# Backplane_Breakout_Adapter_Connectors.net
KiCad netlist of a schematic drawn in Altium Designer
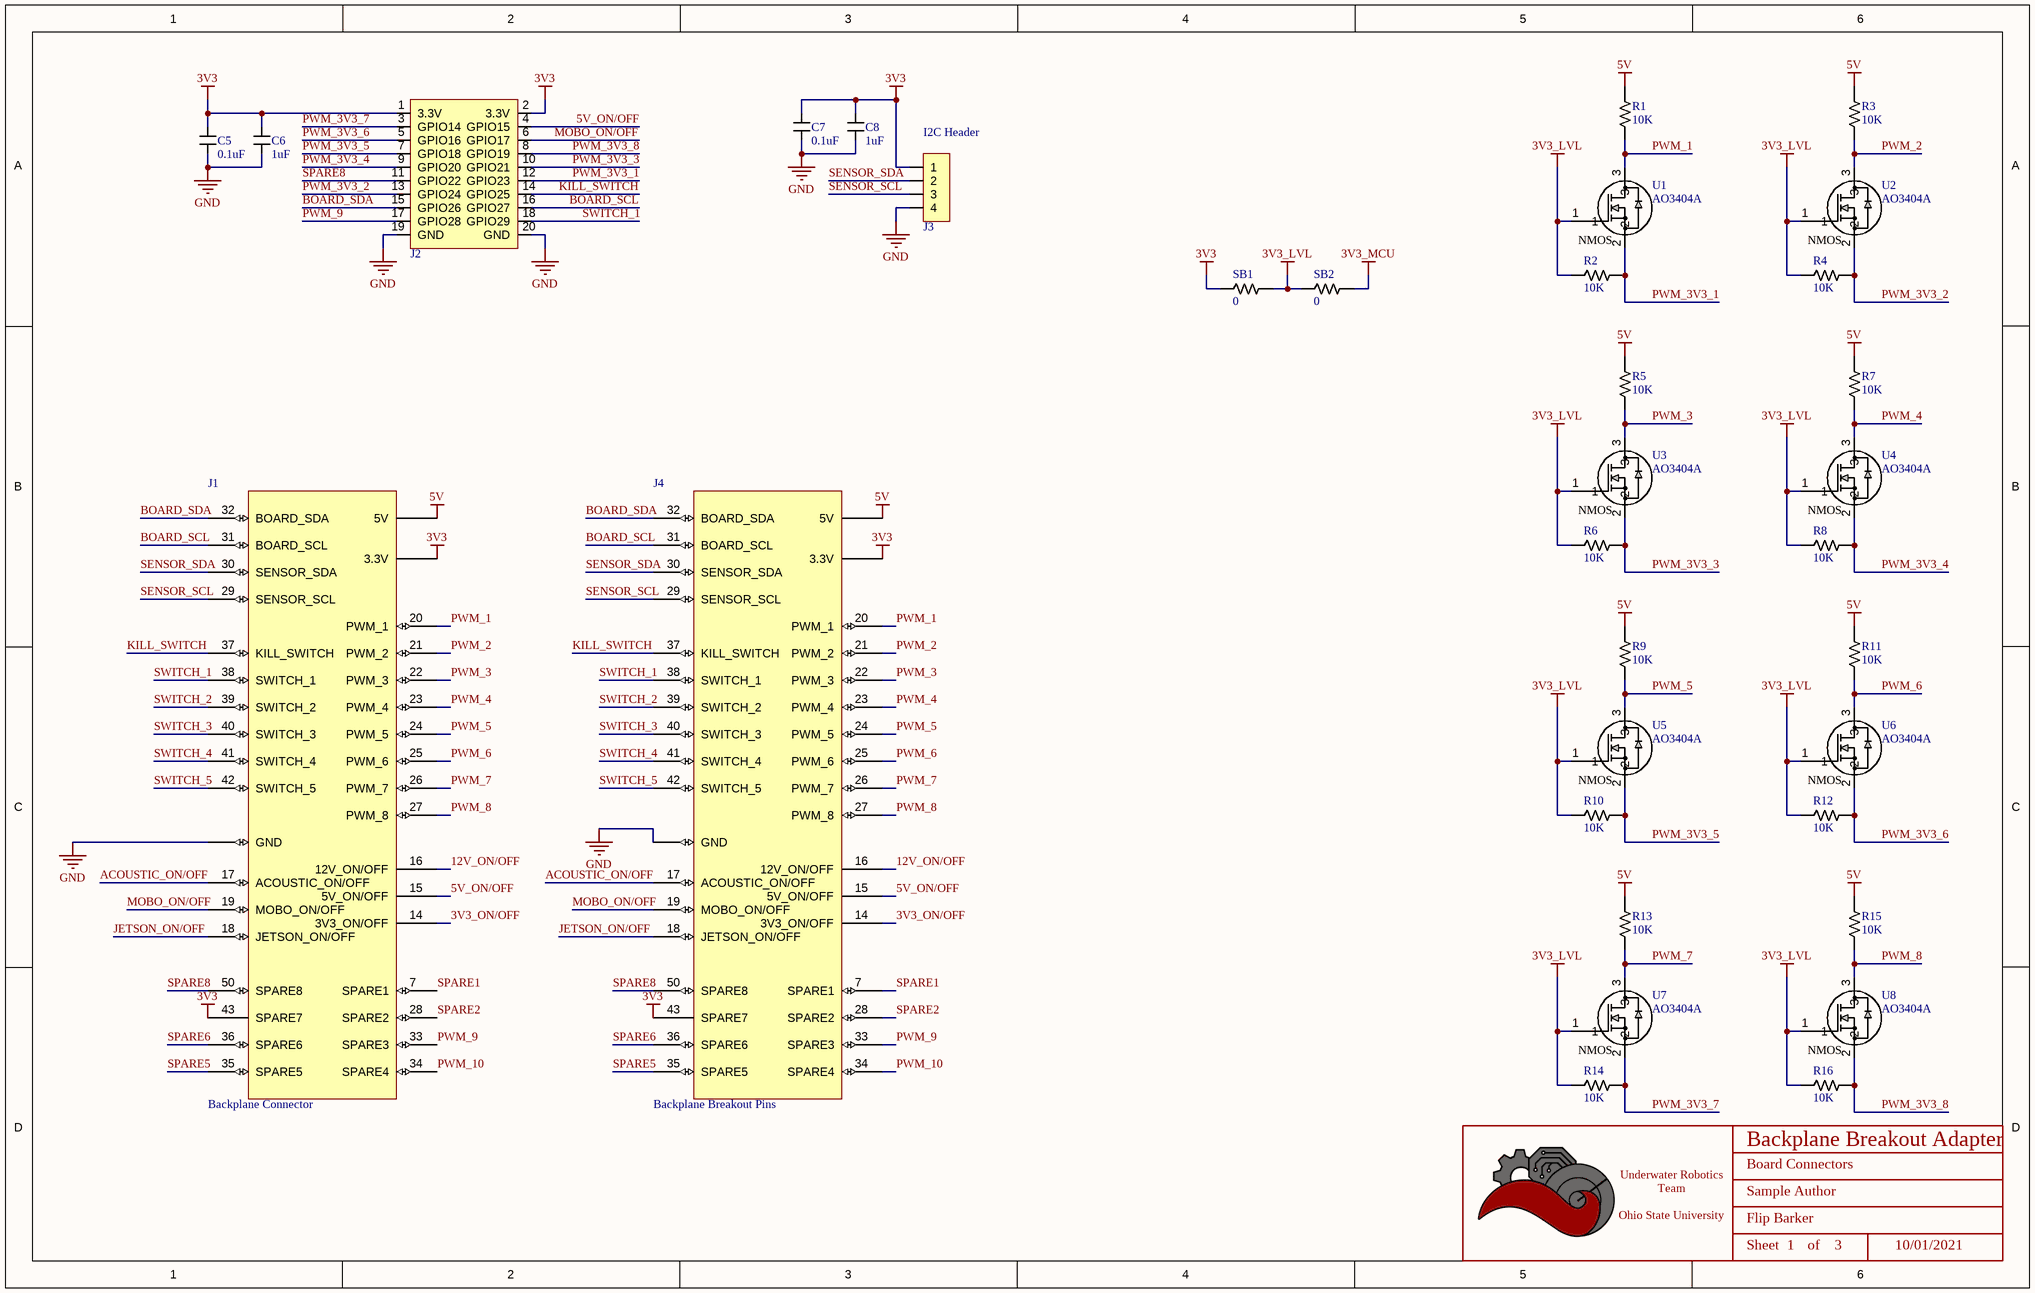
[diagram p0: Backplane_Breakout_Adapter_Connectors.SchDoc]

(export (version "E")
  (design (tool "Eeschema 10.0.6"))
  (components
    (comp (ref "*")
      (value "Title_Block")
      (footprint "LOGO")
      (description "UWRT Schematic Title Block Template\r\n\r\nCreated June 2021, Dylan Trainor")
      (libsource (lib "UWRT") (part "Title_Block"))
    )
    (comp (ref "C5")
      (value "0.1uF")
      (footprint "CAPACITOR_0603")
      (description "Cap 100nF 6.3V +/-10%\r\nCeramic 0603")
      (fields
        (field (name "TOLERANCE") "+/- 10%")
        (field (name "VOLTAGE") "6.3V")
        (field (name "MADE BY") "Flip B")
      )
      (libsource (lib "Capacitors") (part "CAPACITOR_0.1uF_0603"))
    )
    (comp (ref "C6")
      (value "1uF")
      (footprint "CAPACITOR_0603")
      (description "Cap 1uF 16V +/-10%\r\nCeramic 0603")
      (fields
        (field (name "TOLERANCE") "+/- 10%")
        (field (name "VOLTAGE") "16V")
        (field (name "MADE BY") "Flip B")
      )
      (libsource (lib "Capacitors") (part "CAPACITOR_1uF_0603"))
    )
    (comp (ref "C7")
      (value "0.1uF")
      (footprint "CAPACITOR_0603")
      (description "Cap 100nF 6.3V +/-10%\r\nCeramic 0603")
      (fields
        (field (name "TOLERANCE") "+/- 10%")
        (field (name "VOLTAGE") "6.3V")
        (field (name "MADE BY") "Flip B")
      )
      (libsource (lib "Capacitors") (part "CAPACITOR_0.1uF_0603"))
    )
    (comp (ref "C8")
      (value "1uF")
      (footprint "CAPACITOR_0603")
      (description "Cap 1uF 16V +/-10%\r\nCeramic 0603")
      (fields
        (field (name "TOLERANCE") "+/- 10%")
        (field (name "VOLTAGE") "16V")
        (field (name "MADE BY") "Flip B")
      )
      (libsource (lib "Capacitors") (part "CAPACITOR_1uF_0603"))
    )
    (comp (ref "J1")
      (value "Backplane Connector")
      (footprint "BACKPLANE_EDGE_CONN")
      (description "Titan Backplane Edge Connector")
      (libsource (lib "Connectors") (part "BACKBOARD_EDGE_CONN"))
    )
    (comp (ref "J2")
      (value "RP2040 GPIO Header")
      (footprint "HEADER_MIRRORED_2x10PIN_2.54MM")
      (description "CONN HEADER VERT 20POS 2.54MM")
      (fields (field (name "MADE BY") "Robert Pafford"))
      (libsource (lib "Connectors") (part "HEADER_2x10PIN_2.54MM_RP2040_GPIO"))
    )
    (comp (ref "J3")
      (value "CONN HEADER VERT 4POS 2.54MM")
      (footprint "HEADER_MIRRORED_4PIN_2.54MM")
      (fields (field (name "MADE BY") "Robert Pafford"))
      (libsource (lib "Connectors") (part "HEADER_4PIN_2.54MM"))
    )
    (comp (ref "J4")
      (value "Backplane Breakout Pins")
      (footprint "HEADER_2X28PIN_2.54MM")
      (description "Titan Backplane Edge Connector")
      (libsource (lib "Connectors") (part "BACKBOARD_EDGE_CONN"))
    )
    (comp (ref "R1")
      (value "10k Ohm 5% 1/10W")
      (footprint "RESISTOR_0603")
      (description "RES 10k OHM 5% 1/10W 0603")
      (fields
        (field (name "TOLERANCE") "+/- 5%")
        (field (name "VALUE  (OHMS)") "10K")
        (field (name "MADE BY") "Robert Pafford")
      )
      (libsource (lib "Resistors") (part "RESISTOR_10K_0603"))
    )
    (comp (ref "R2")
      (value "10k Ohm 5% 1/10W")
      (footprint "RESISTOR_0603")
      (description "RES 10k OHM 5% 1/10W 0603")
      (fields
        (field (name "TOLERANCE") "+/- 5%")
        (field (name "VALUE  (OHMS)") "10K")
        (field (name "MADE BY") "Robert Pafford")
      )
      (libsource (lib "Resistors") (part "RESISTOR_10K_0603"))
    )
    (comp (ref "R3")
      (value "10k Ohm 5% 1/10W")
      (footprint "RESISTOR_0603")
      (description "RES 10k OHM 5% 1/10W 0603")
      (fields
        (field (name "TOLERANCE") "+/- 5%")
        (field (name "VALUE  (OHMS)") "10K")
        (field (name "MADE BY") "Robert Pafford")
      )
      (libsource (lib "Resistors") (part "RESISTOR_10K_0603"))
    )
    (comp (ref "R4")
      (value "10k Ohm 5% 1/10W")
      (footprint "RESISTOR_0603")
      (description "RES 10k OHM 5% 1/10W 0603")
      (fields
        (field (name "TOLERANCE") "+/- 5%")
        (field (name "VALUE  (OHMS)") "10K")
        (field (name "MADE BY") "Robert Pafford")
      )
      (libsource (lib "Resistors") (part "RESISTOR_10K_0603"))
    )
    (comp (ref "R5")
      (value "10k Ohm 5% 1/10W")
      (footprint "RESISTOR_0603")
      (description "RES 10k OHM 5% 1/10W 0603")
      (fields
        (field (name "TOLERANCE") "+/- 5%")
        (field (name "VALUE  (OHMS)") "10K")
        (field (name "MADE BY") "Robert Pafford")
      )
      (libsource (lib "Resistors") (part "RESISTOR_10K_0603"))
    )
    (comp (ref "R6")
      (value "10k Ohm 5% 1/10W")
      (footprint "RESISTOR_0603")
      (description "RES 10k OHM 5% 1/10W 0603")
      (fields
        (field (name "TOLERANCE") "+/- 5%")
        (field (name "VALUE  (OHMS)") "10K")
        (field (name "MADE BY") "Robert Pafford")
      )
      (libsource (lib "Resistors") (part "RESISTOR_10K_0603"))
    )
    (comp (ref "R7")
      (value "10k Ohm 5% 1/10W")
      (footprint "RESISTOR_0603")
      (description "RES 10k OHM 5% 1/10W 0603")
      (fields
        (field (name "TOLERANCE") "+/- 5%")
        (field (name "VALUE  (OHMS)") "10K")
        (field (name "MADE BY") "Robert Pafford")
      )
      (libsource (lib "Resistors") (part "RESISTOR_10K_0603"))
    )
    (comp (ref "R8")
      (value "10k Ohm 5% 1/10W")
      (footprint "RESISTOR_0603")
      (description "RES 10k OHM 5% 1/10W 0603")
      (fields
        (field (name "TOLERANCE") "+/- 5%")
        (field (name "VALUE  (OHMS)") "10K")
        (field (name "MADE BY") "Robert Pafford")
      )
      (libsource (lib "Resistors") (part "RESISTOR_10K_0603"))
    )
    (comp (ref "R9")
      (value "10k Ohm 5% 1/10W")
      (footprint "RESISTOR_0603")
      (description "RES 10k OHM 5% 1/10W 0603")
      (fields
        (field (name "TOLERANCE") "+/- 5%")
        (field (name "VALUE  (OHMS)") "10K")
        (field (name "MADE BY") "Robert Pafford")
      )
      (libsource (lib "Resistors") (part "RESISTOR_10K_0603"))
    )
    (comp (ref "R10")
      (value "10k Ohm 5% 1/10W")
      (footprint "RESISTOR_0603")
      (description "RES 10k OHM 5% 1/10W 0603")
      (fields
        (field (name "TOLERANCE") "+/- 5%")
        (field (name "VALUE  (OHMS)") "10K")
        (field (name "MADE BY") "Robert Pafford")
      )
      (libsource (lib "Resistors") (part "RESISTOR_10K_0603"))
    )
    (comp (ref "R11")
      (value "10k Ohm 5% 1/10W")
      (footprint "RESISTOR_0603")
      (description "RES 10k OHM 5% 1/10W 0603")
      (fields
        (field (name "TOLERANCE") "+/- 5%")
        (field (name "VALUE  (OHMS)") "10K")
        (field (name "MADE BY") "Robert Pafford")
      )
      (libsource (lib "Resistors") (part "RESISTOR_10K_0603"))
    )
    (comp (ref "R12")
      (value "10k Ohm 5% 1/10W")
      (footprint "RESISTOR_0603")
      (description "RES 10k OHM 5% 1/10W 0603")
      (fields
        (field (name "TOLERANCE") "+/- 5%")
        (field (name "VALUE  (OHMS)") "10K")
        (field (name "MADE BY") "Robert Pafford")
      )
      (libsource (lib "Resistors") (part "RESISTOR_10K_0603"))
    )
    (comp (ref "R13")
      (value "10k Ohm 5% 1/10W")
      (footprint "RESISTOR_0603")
      (description "RES 10k OHM 5% 1/10W 0603")
      (fields
        (field (name "TOLERANCE") "+/- 5%")
        (field (name "VALUE  (OHMS)") "10K")
        (field (name "MADE BY") "Robert Pafford")
      )
      (libsource (lib "Resistors") (part "RESISTOR_10K_0603"))
    )
    (comp (ref "R14")
      (value "10k Ohm 5% 1/10W")
      (footprint "RESISTOR_0603")
      (description "RES 10k OHM 5% 1/10W 0603")
      (fields
        (field (name "TOLERANCE") "+/- 5%")
        (field (name "VALUE  (OHMS)") "10K")
        (field (name "MADE BY") "Robert Pafford")
      )
      (libsource (lib "Resistors") (part "RESISTOR_10K_0603"))
    )
    (comp (ref "R15")
      (value "10k Ohm 5% 1/10W")
      (footprint "RESISTOR_0603")
      (description "RES 10k OHM 5% 1/10W 0603")
      (fields
        (field (name "TOLERANCE") "+/- 5%")
        (field (name "VALUE  (OHMS)") "10K")
        (field (name "MADE BY") "Robert Pafford")
      )
      (libsource (lib "Resistors") (part "RESISTOR_10K_0603"))
    )
    (comp (ref "R16")
      (value "10k Ohm 5% 1/10W")
      (footprint "RESISTOR_0603")
      (description "RES 10k OHM 5% 1/10W 0603")
      (fields
        (field (name "TOLERANCE") "+/- 5%")
        (field (name "VALUE  (OHMS)") "10K")
        (field (name "MADE BY") "Robert Pafford")
      )
      (libsource (lib "Resistors") (part "RESISTOR_10K_0603"))
    )
    (comp (ref "SB1")
      (value "0 Ohm Jumper No Fit")
      (footprint "RESISTOR_0603")
      (description "0 Ohm Jumper No Fit for Solder Bridge")
      (fields (field (name "VALUE  (OHMS)") "0") (field (name "MADE BY") "Robert Pafford"))
      (libsource (lib "Resistors") (part "JUMPER_0_0603"))
    )
    (comp (ref "SB2")
      (value "0 Ohm Jumper No Fit")
      (footprint "RESISTOR_0603")
      (description "0 Ohm Jumper No Fit for Solder Bridge")
      (fields (field (name "VALUE  (OHMS)") "0") (field (name "MADE BY") "Robert Pafford"))
      (libsource (lib "Resistors") (part "JUMPER_0_0603"))
    )
    (comp (ref "U1")
      (value "AO3404A")
      (footprint "SOT-23-3")
      (description "N-Channel 30 V 5.8A (Ta) 1.4W (Ta) Surface Mount SOT-23-3")
      (fields (field (name "CREATED BY") "Dylan T"))
      (libsource (lib "Transistors") (part "AO3404A"))
    )
    (comp (ref "U2")
      (value "AO3404A")
      (footprint "SOT-23-3")
      (description "N-Channel 30 V 5.8A (Ta) 1.4W (Ta) Surface Mount SOT-23-3")
      (fields (field (name "CREATED BY") "Dylan T"))
      (libsource (lib "Transistors") (part "AO3404A"))
    )
    (comp (ref "U3")
      (value "AO3404A")
      (footprint "SOT-23-3")
      (description "N-Channel 30 V 5.8A (Ta) 1.4W (Ta) Surface Mount SOT-23-3")
      (fields (field (name "CREATED BY") "Dylan T"))
      (libsource (lib "Transistors") (part "AO3404A"))
    )
    (comp (ref "U4")
      (value "AO3404A")
      (footprint "SOT-23-3")
      (description "N-Channel 30 V 5.8A (Ta) 1.4W (Ta) Surface Mount SOT-23-3")
      (fields (field (name "CREATED BY") "Dylan T"))
      (libsource (lib "Transistors") (part "AO3404A"))
    )
    (comp (ref "U5")
      (value "AO3404A")
      (footprint "SOT-23-3")
      (description "N-Channel 30 V 5.8A (Ta) 1.4W (Ta) Surface Mount SOT-23-3")
      (fields (field (name "CREATED BY") "Dylan T"))
      (libsource (lib "Transistors") (part "AO3404A"))
    )
    (comp (ref "U6")
      (value "AO3404A")
      (footprint "SOT-23-3")
      (description "N-Channel 30 V 5.8A (Ta) 1.4W (Ta) Surface Mount SOT-23-3")
      (fields (field (name "CREATED BY") "Dylan T"))
      (libsource (lib "Transistors") (part "AO3404A"))
    )
    (comp (ref "U7")
      (value "AO3404A")
      (footprint "SOT-23-3")
      (description "N-Channel 30 V 5.8A (Ta) 1.4W (Ta) Surface Mount SOT-23-3")
      (fields (field (name "CREATED BY") "Dylan T"))
      (libsource (lib "Transistors") (part "AO3404A"))
    )
    (comp (ref "U8")
      (value "AO3404A")
      (footprint "SOT-23-3")
      (description "N-Channel 30 V 5.8A (Ta) 1.4W (Ta) Surface Mount SOT-23-3")
      (fields (field (name "CREATED BY") "Dylan T"))
      (libsource (lib "Transistors") (part "AO3404A"))
    )
  )
  (nets
    (net (code "1") (name "/3V3_ON{slash}OFF") (class "Default")
      (node (ref "J1") (pin "14") (pinfunction "3V3_ON/OFF_14") (pintype "power_in"))
      (node (ref "J4") (pin "14") (pinfunction "3V3_ON/OFF_14") (pintype "power_in"))
    )
    (net (code "2") (name "/5V_ON{slash}OFF") (class "Default")
      (node (ref "J1") (pin "15") (pinfunction "5V_ON/OFF_15") (pintype "power_in"))
      (node (ref "J2") (pin "4") (pinfunction "GPIO15_4") (pintype "bidirectional"))
      (node (ref "J4") (pin "15") (pinfunction "5V_ON/OFF_15") (pintype "power_in"))
    )
    (net (code "3") (name "/12V_ON{slash}OFF") (class "Default")
      (node (ref "J1") (pin "16") (pinfunction "12V_ON/OFF_16") (pintype "power_in"))
      (node (ref "J4") (pin "16") (pinfunction "12V_ON/OFF_16") (pintype "power_in"))
    )
    (net (code "4") (name "/ACOUSTIC_ON{slash}OFF") (class "Default")
      (node (ref "J1") (pin "17") (pinfunction "ACOUSTIC_ON/OFF_17") (pintype "bidirectional"))
      (node (ref "J4") (pin "17") (pinfunction "ACOUSTIC_ON/OFF_17") (pintype "bidirectional"))
    )
    (net (code "5") (name "/BOARD_SCL") (class "Default")
      (node (ref "J1") (pin "31") (pinfunction "BOARD_SCL_31") (pintype "bidirectional"))
      (node (ref "J2") (pin "16") (pinfunction "GPIO27_16") (pintype "bidirectional"))
      (node (ref "J4") (pin "31") (pinfunction "BOARD_SCL_31") (pintype "bidirectional"))
    )
    (net (code "6") (name "/BOARD_SDA") (class "Default")
      (node (ref "J1") (pin "32") (pinfunction "BOARD_SDA_32") (pintype "bidirectional"))
      (node (ref "J2") (pin "15") (pinfunction "GPIO26_15") (pintype "bidirectional"))
      (node (ref "J4") (pin "32") (pinfunction "BOARD_SDA_32") (pintype "bidirectional"))
    )
    (net (code "7") (name "/JETSON_ON{slash}OFF") (class "Default")
      (node (ref "J1") (pin "18") (pinfunction "JETSON_ON/OFF_18") (pintype "bidirectional"))
      (node (ref "J4") (pin "18") (pinfunction "JETSON_ON/OFF_18") (pintype "bidirectional"))
    )
    (net (code "8") (name "/KILL_SWITCH") (class "Default")
      (node (ref "J1") (pin "37") (pinfunction "KILL_SWITCH_37") (pintype "bidirectional"))
      (node (ref "J2") (pin "14") (pinfunction "GPIO25_14") (pintype "bidirectional"))
      (node (ref "J4") (pin "37") (pinfunction "KILL_SWITCH_37") (pintype "bidirectional"))
    )
    (net (code "9") (name "/MOBO_ON{slash}OFF") (class "Default")
      (node (ref "J1") (pin "19") (pinfunction "MOBO_ON/OFF_19") (pintype "bidirectional"))
      (node (ref "J2") (pin "6") (pinfunction "GPIO17_6") (pintype "bidirectional"))
      (node (ref "J4") (pin "19") (pinfunction "MOBO_ON/OFF_19") (pintype "bidirectional"))
    )
    (net (code "10") (name "/PWM_1") (class "Default")
      (node (ref "J1") (pin "20") (pinfunction "PWM_1_20") (pintype "bidirectional"))
      (node (ref "J4") (pin "20") (pinfunction "PWM_1_20") (pintype "bidirectional"))
      (node (ref "R1") (pin "2") (pinfunction "2_2") (pintype "passive"))
      (node (ref "U1") (pin "3") (pinfunction "3_3") (pintype "passive"))
    )
    (net (code "11") (name "/PWM_2") (class "Default")
      (node (ref "J1") (pin "21") (pinfunction "PWM_2_21") (pintype "bidirectional"))
      (node (ref "J4") (pin "21") (pinfunction "PWM_2_21") (pintype "bidirectional"))
      (node (ref "R3") (pin "2") (pinfunction "2_2") (pintype "passive"))
      (node (ref "U2") (pin "3") (pinfunction "3_3") (pintype "passive"))
    )
    (net (code "12") (name "/PWM_3") (class "Default")
      (node (ref "J1") (pin "22") (pinfunction "PWM_3_22") (pintype "bidirectional"))
      (node (ref "J4") (pin "22") (pinfunction "PWM_3_22") (pintype "bidirectional"))
      (node (ref "R5") (pin "2") (pinfunction "2_2") (pintype "passive"))
      (node (ref "U3") (pin "3") (pinfunction "3_3") (pintype "passive"))
    )
    (net (code "13") (name "/PWM_3V3_1") (class "Default")
      (node (ref "J2") (pin "12") (pinfunction "GPIO23_12") (pintype "bidirectional"))
      (node (ref "R2") (pin "1") (pinfunction "1_1") (pintype "passive"))
      (node (ref "U1") (pin "2") (pinfunction "2_2") (pintype "passive"))
    )
    (net (code "14") (name "/PWM_3V3_2") (class "Default")
      (node (ref "J2") (pin "13") (pinfunction "GPIO24_13") (pintype "bidirectional"))
      (node (ref "R4") (pin "1") (pinfunction "1_1") (pintype "passive"))
      (node (ref "U2") (pin "2") (pinfunction "2_2") (pintype "passive"))
    )
    (net (code "15") (name "/PWM_3V3_3") (class "Default")
      (node (ref "J2") (pin "10") (pinfunction "GPIO21_10") (pintype "bidirectional"))
      (node (ref "R6") (pin "1") (pinfunction "1_1") (pintype "passive"))
      (node (ref "U3") (pin "2") (pinfunction "2_2") (pintype "passive"))
    )
    (net (code "16") (name "/PWM_3V3_4") (class "Default")
      (node (ref "J2") (pin "9") (pinfunction "GPIO20_9") (pintype "bidirectional"))
      (node (ref "R8") (pin "1") (pinfunction "1_1") (pintype "passive"))
      (node (ref "U4") (pin "2") (pinfunction "2_2") (pintype "passive"))
    )
    (net (code "17") (name "/PWM_3V3_5") (class "Default")
      (node (ref "J2") (pin "7") (pinfunction "GPIO18_7") (pintype "bidirectional"))
      (node (ref "R10") (pin "1") (pinfunction "1_1") (pintype "passive"))
      (node (ref "U5") (pin "2") (pinfunction "2_2") (pintype "passive"))
    )
    (net (code "18") (name "/PWM_3V3_6") (class "Default")
      (node (ref "J2") (pin "5") (pinfunction "GPIO16_5") (pintype "bidirectional"))
      (node (ref "R12") (pin "1") (pinfunction "1_1") (pintype "passive"))
      (node (ref "U6") (pin "2") (pinfunction "2_2") (pintype "passive"))
    )
    (net (code "19") (name "/PWM_3V3_7") (class "Default")
      (node (ref "J2") (pin "3") (pinfunction "GPIO14_3") (pintype "bidirectional"))
      (node (ref "R14") (pin "1") (pinfunction "1_1") (pintype "passive"))
      (node (ref "U7") (pin "2") (pinfunction "2_2") (pintype "passive"))
    )
    (net (code "20") (name "/PWM_3V3_8") (class "Default")
      (node (ref "J2") (pin "8") (pinfunction "GPIO19_8") (pintype "bidirectional"))
      (node (ref "R16") (pin "1") (pinfunction "1_1") (pintype "passive"))
      (node (ref "U8") (pin "2") (pinfunction "2_2") (pintype "passive"))
    )
    (net (code "21") (name "/PWM_4") (class "Default")
      (node (ref "J1") (pin "23") (pinfunction "PWM_4_23") (pintype "bidirectional"))
      (node (ref "J4") (pin "23") (pinfunction "PWM_4_23") (pintype "bidirectional"))
      (node (ref "R7") (pin "2") (pinfunction "2_2") (pintype "passive"))
      (node (ref "U4") (pin "3") (pinfunction "3_3") (pintype "passive"))
    )
    (net (code "22") (name "/PWM_5") (class "Default")
      (node (ref "J1") (pin "24") (pinfunction "PWM_5_24") (pintype "bidirectional"))
      (node (ref "J4") (pin "24") (pinfunction "PWM_5_24") (pintype "bidirectional"))
      (node (ref "R9") (pin "2") (pinfunction "2_2") (pintype "passive"))
      (node (ref "U5") (pin "3") (pinfunction "3_3") (pintype "passive"))
    )
    (net (code "23") (name "/PWM_6") (class "Default")
      (node (ref "J1") (pin "25") (pinfunction "PWM_6_25") (pintype "bidirectional"))
      (node (ref "J4") (pin "25") (pinfunction "PWM_6_25") (pintype "bidirectional"))
      (node (ref "R11") (pin "2") (pinfunction "2_2") (pintype "passive"))
      (node (ref "U6") (pin "3") (pinfunction "3_3") (pintype "passive"))
    )
    (net (code "24") (name "/PWM_7") (class "Default")
      (node (ref "J1") (pin "26") (pinfunction "PWM_7_26") (pintype "bidirectional"))
      (node (ref "J4") (pin "26") (pinfunction "PWM_7_26") (pintype "bidirectional"))
      (node (ref "R13") (pin "2") (pinfunction "2_2") (pintype "passive"))
      (node (ref "U7") (pin "3") (pinfunction "3_3") (pintype "passive"))
    )
    (net (code "25") (name "/PWM_8") (class "Default")
      (node (ref "J1") (pin "27") (pinfunction "PWM_8_27") (pintype "bidirectional"))
      (node (ref "J4") (pin "27") (pinfunction "PWM_8_27") (pintype "bidirectional"))
      (node (ref "R15") (pin "2") (pinfunction "2_2") (pintype "passive"))
      (node (ref "U8") (pin "3") (pinfunction "3_3") (pintype "passive"))
    )
    (net (code "26") (name "/PWM_9") (class "Default")
      (node (ref "J1") (pin "33") (pinfunction "SPARE3_33") (pintype "bidirectional"))
      (node (ref "J2") (pin "17") (pinfunction "GPIO28_17") (pintype "bidirectional"))
      (node (ref "J4") (pin "33") (pinfunction "SPARE3_33") (pintype "bidirectional"))
    )
    (net (code "27") (name "/PWM_10") (class "Default")
      (node (ref "J1") (pin "34") (pinfunction "SPARE4_34") (pintype "bidirectional"))
      (node (ref "J4") (pin "34") (pinfunction "SPARE4_34") (pintype "bidirectional"))
    )
    (net (code "28") (name "/SENSOR_SCL") (class "Default")
      (node (ref "J1") (pin "29") (pinfunction "SENSOR_SCL_29") (pintype "bidirectional"))
      (node (ref "J3") (pin "3") (pinfunction "3_3") (pintype "passive"))
      (node (ref "J4") (pin "29") (pinfunction "SENSOR_SCL_29") (pintype "bidirectional"))
    )
    (net (code "29") (name "/SENSOR_SDA") (class "Default")
      (node (ref "J1") (pin "30") (pinfunction "SENSOR_SDA_30") (pintype "bidirectional"))
      (node (ref "J3") (pin "2") (pinfunction "2_2") (pintype "passive"))
      (node (ref "J4") (pin "30") (pinfunction "SENSOR_SDA_30") (pintype "bidirectional"))
    )
    (net (code "30") (name "/SPARE1") (class "Default")
      (node (ref "J1") (pin "7") (pinfunction "SPARE1_7") (pintype "bidirectional"))
      (node (ref "J4") (pin "7") (pinfunction "SPARE1_7") (pintype "bidirectional"))
    )
    (net (code "31") (name "/SPARE2") (class "Default")
      (node (ref "J1") (pin "28") (pinfunction "SPARE2_28") (pintype "bidirectional"))
      (node (ref "J4") (pin "28") (pinfunction "SPARE2_28") (pintype "bidirectional"))
    )
    (net (code "32") (name "/SPARE5") (class "Default")
      (node (ref "J1") (pin "35") (pinfunction "SPARE5_35") (pintype "bidirectional"))
      (node (ref "J4") (pin "35") (pinfunction "SPARE5_35") (pintype "bidirectional"))
    )
    (net (code "33") (name "/SPARE6") (class "Default")
      (node (ref "J1") (pin "36") (pinfunction "SPARE6_36") (pintype "bidirectional"))
      (node (ref "J4") (pin "36") (pinfunction "SPARE6_36") (pintype "bidirectional"))
    )
    (net (code "34") (name "/SPARE8") (class "Default")
      (node (ref "J1") (pin "50") (pinfunction "SPARE8_50") (pintype "bidirectional"))
      (node (ref "J2") (pin "11") (pinfunction "GPIO22_11") (pintype "bidirectional"))
      (node (ref "J4") (pin "50") (pinfunction "SPARE8_50") (pintype "bidirectional"))
    )
    (net (code "35") (name "/SWITCH_1") (class "Default")
      (node (ref "J1") (pin "38") (pinfunction "SWITCH_1_38") (pintype "bidirectional"))
      (node (ref "J2") (pin "18") (pinfunction "GPIO29_18") (pintype "bidirectional"))
      (node (ref "J4") (pin "38") (pinfunction "SWITCH_1_38") (pintype "bidirectional"))
    )
    (net (code "36") (name "/SWITCH_2") (class "Default")
      (node (ref "J1") (pin "39") (pinfunction "SWITCH_2_39") (pintype "bidirectional"))
      (node (ref "J4") (pin "39") (pinfunction "SWITCH_2_39") (pintype "bidirectional"))
    )
    (net (code "37") (name "/SWITCH_3") (class "Default")
      (node (ref "J1") (pin "40") (pinfunction "SWITCH_3_40") (pintype "bidirectional"))
      (node (ref "J4") (pin "40") (pinfunction "SWITCH_3_40") (pintype "bidirectional"))
    )
    (net (code "38") (name "/SWITCH_4") (class "Default")
      (node (ref "J1") (pin "41") (pinfunction "SWITCH_4_41") (pintype "bidirectional"))
      (node (ref "J4") (pin "41") (pinfunction "SWITCH_4_41") (pintype "bidirectional"))
    )
    (net (code "39") (name "/SWITCH_5") (class "Default")
      (node (ref "J1") (pin "42") (pinfunction "SWITCH_5_42") (pintype "bidirectional"))
      (node (ref "J4") (pin "42") (pinfunction "SWITCH_5_42") (pintype "bidirectional"))
    )
    (net (code "40") (name "3V3") (class "Default")
      (node (ref "C5") (pin "1") (pinfunction "1_1") (pintype "passive"))
      (node (ref "C6") (pin "1") (pinfunction "1_1") (pintype "passive"))
      (node (ref "C7") (pin "1") (pinfunction "1_1") (pintype "passive"))
      (node (ref "C8") (pin "1") (pinfunction "1_1") (pintype "passive"))
      (node (ref "J1") (pin "1*6") (pinfunction "3.3V_1*6") (pintype "power_in"))
      (node (ref "J1") (pin "43") (pinfunction "SPARE7_43") (pintype "power_in"))
      (node (ref "J2") (pin "1") (pinfunction "3.3V_1") (pintype "power_in"))
      (node (ref "J2") (pin "2") (pinfunction "3.3V_2") (pintype "power_in"))
      (node (ref "J3") (pin "1") (pinfunction "1_1") (pintype "passive"))
      (node (ref "J4") (pin "1*6") (pinfunction "3.3V_1*6") (pintype "power_in"))
      (node (ref "J4") (pin "43") (pinfunction "SPARE7_43") (pintype "power_in"))
      (node (ref "SB1") (pin "2") (pinfunction "2_2") (pintype "passive"))
    )
    (net (code "41") (name "3V3_LVL") (class "Default")
      (node (ref "R10") (pin "2") (pinfunction "2_2") (pintype "passive"))
      (node (ref "R12") (pin "2") (pinfunction "2_2") (pintype "passive"))
      (node (ref "R14") (pin "2") (pinfunction "2_2") (pintype "passive"))
      (node (ref "R16") (pin "2") (pinfunction "2_2") (pintype "passive"))
      (node (ref "R2") (pin "2") (pinfunction "2_2") (pintype "passive"))
      (node (ref "R4") (pin "2") (pinfunction "2_2") (pintype "passive"))
      (node (ref "R6") (pin "2") (pinfunction "2_2") (pintype "passive"))
      (node (ref "R8") (pin "2") (pinfunction "2_2") (pintype "passive"))
      (node (ref "SB1") (pin "1") (pinfunction "1_1") (pintype "passive"))
      (node (ref "SB2") (pin "2") (pinfunction "2_2") (pintype "passive"))
      (node (ref "U1") (pin "1") (pinfunction "1_1") (pintype "passive"))
      (node (ref "U2") (pin "1") (pinfunction "1_1") (pintype "passive"))
      (node (ref "U3") (pin "1") (pinfunction "1_1") (pintype "passive"))
      (node (ref "U4") (pin "1") (pinfunction "1_1") (pintype "passive"))
      (node (ref "U5") (pin "1") (pinfunction "1_1") (pintype "passive"))
      (node (ref "U6") (pin "1") (pinfunction "1_1") (pintype "passive"))
      (node (ref "U7") (pin "1") (pinfunction "1_1") (pintype "passive"))
      (node (ref "U8") (pin "1") (pinfunction "1_1") (pintype "passive"))
    )
    (net (code "42") (name "3V3_MCU") (class "Default")
      (node (ref "SB2") (pin "1") (pinfunction "1_1") (pintype "passive"))
    )
    (net (code "43") (name "5V") (class "Default")
      (node (ref "J1") (pin "11*6") (pinfunction "5V_11*6") (pintype "power_in"))
      (node (ref "J4") (pin "11*6") (pinfunction "5V_11*6") (pintype "power_in"))
      (node (ref "R1") (pin "1") (pinfunction "1_1") (pintype "passive"))
      (node (ref "R11") (pin "1") (pinfunction "1_1") (pintype "passive"))
      (node (ref "R13") (pin "1") (pinfunction "1_1") (pintype "passive"))
      (node (ref "R15") (pin "1") (pinfunction "1_1") (pintype "passive"))
      (node (ref "R3") (pin "1") (pinfunction "1_1") (pintype "passive"))
      (node (ref "R5") (pin "1") (pinfunction "1_1") (pintype "passive"))
      (node (ref "R7") (pin "1") (pinfunction "1_1") (pintype "passive"))
      (node (ref "R9") (pin "1") (pinfunction "1_1") (pintype "passive"))
    )
    (net (code "44") (name "GND") (class "Default")
      (node (ref "C5") (pin "2") (pinfunction "2_2") (pintype "passive"))
      (node (ref "C6") (pin "2") (pinfunction "2_2") (pintype "passive"))
      (node (ref "C7") (pin "2") (pinfunction "2_2") (pintype "passive"))
      (node (ref "C8") (pin "2") (pinfunction "2_2") (pintype "passive"))
      (node (ref "J1") (pin "4*12") (pinfunction "GND_4*12") (pintype "bidirectional"))
      (node (ref "J2") (pin "19") (pinfunction "GND_19") (pintype "power_in"))
      (node (ref "J2") (pin "20") (pinfunction "GND_20") (pintype "power_in"))
      (node (ref "J3") (pin "4") (pinfunction "4_4") (pintype "passive"))
      (node (ref "J4") (pin "4*12") (pinfunction "GND_4*12") (pintype "bidirectional"))
    )
  )
)
